# LAN9254_C_P2.net
KiCad netlist of a schematic drawn in Altium Designer
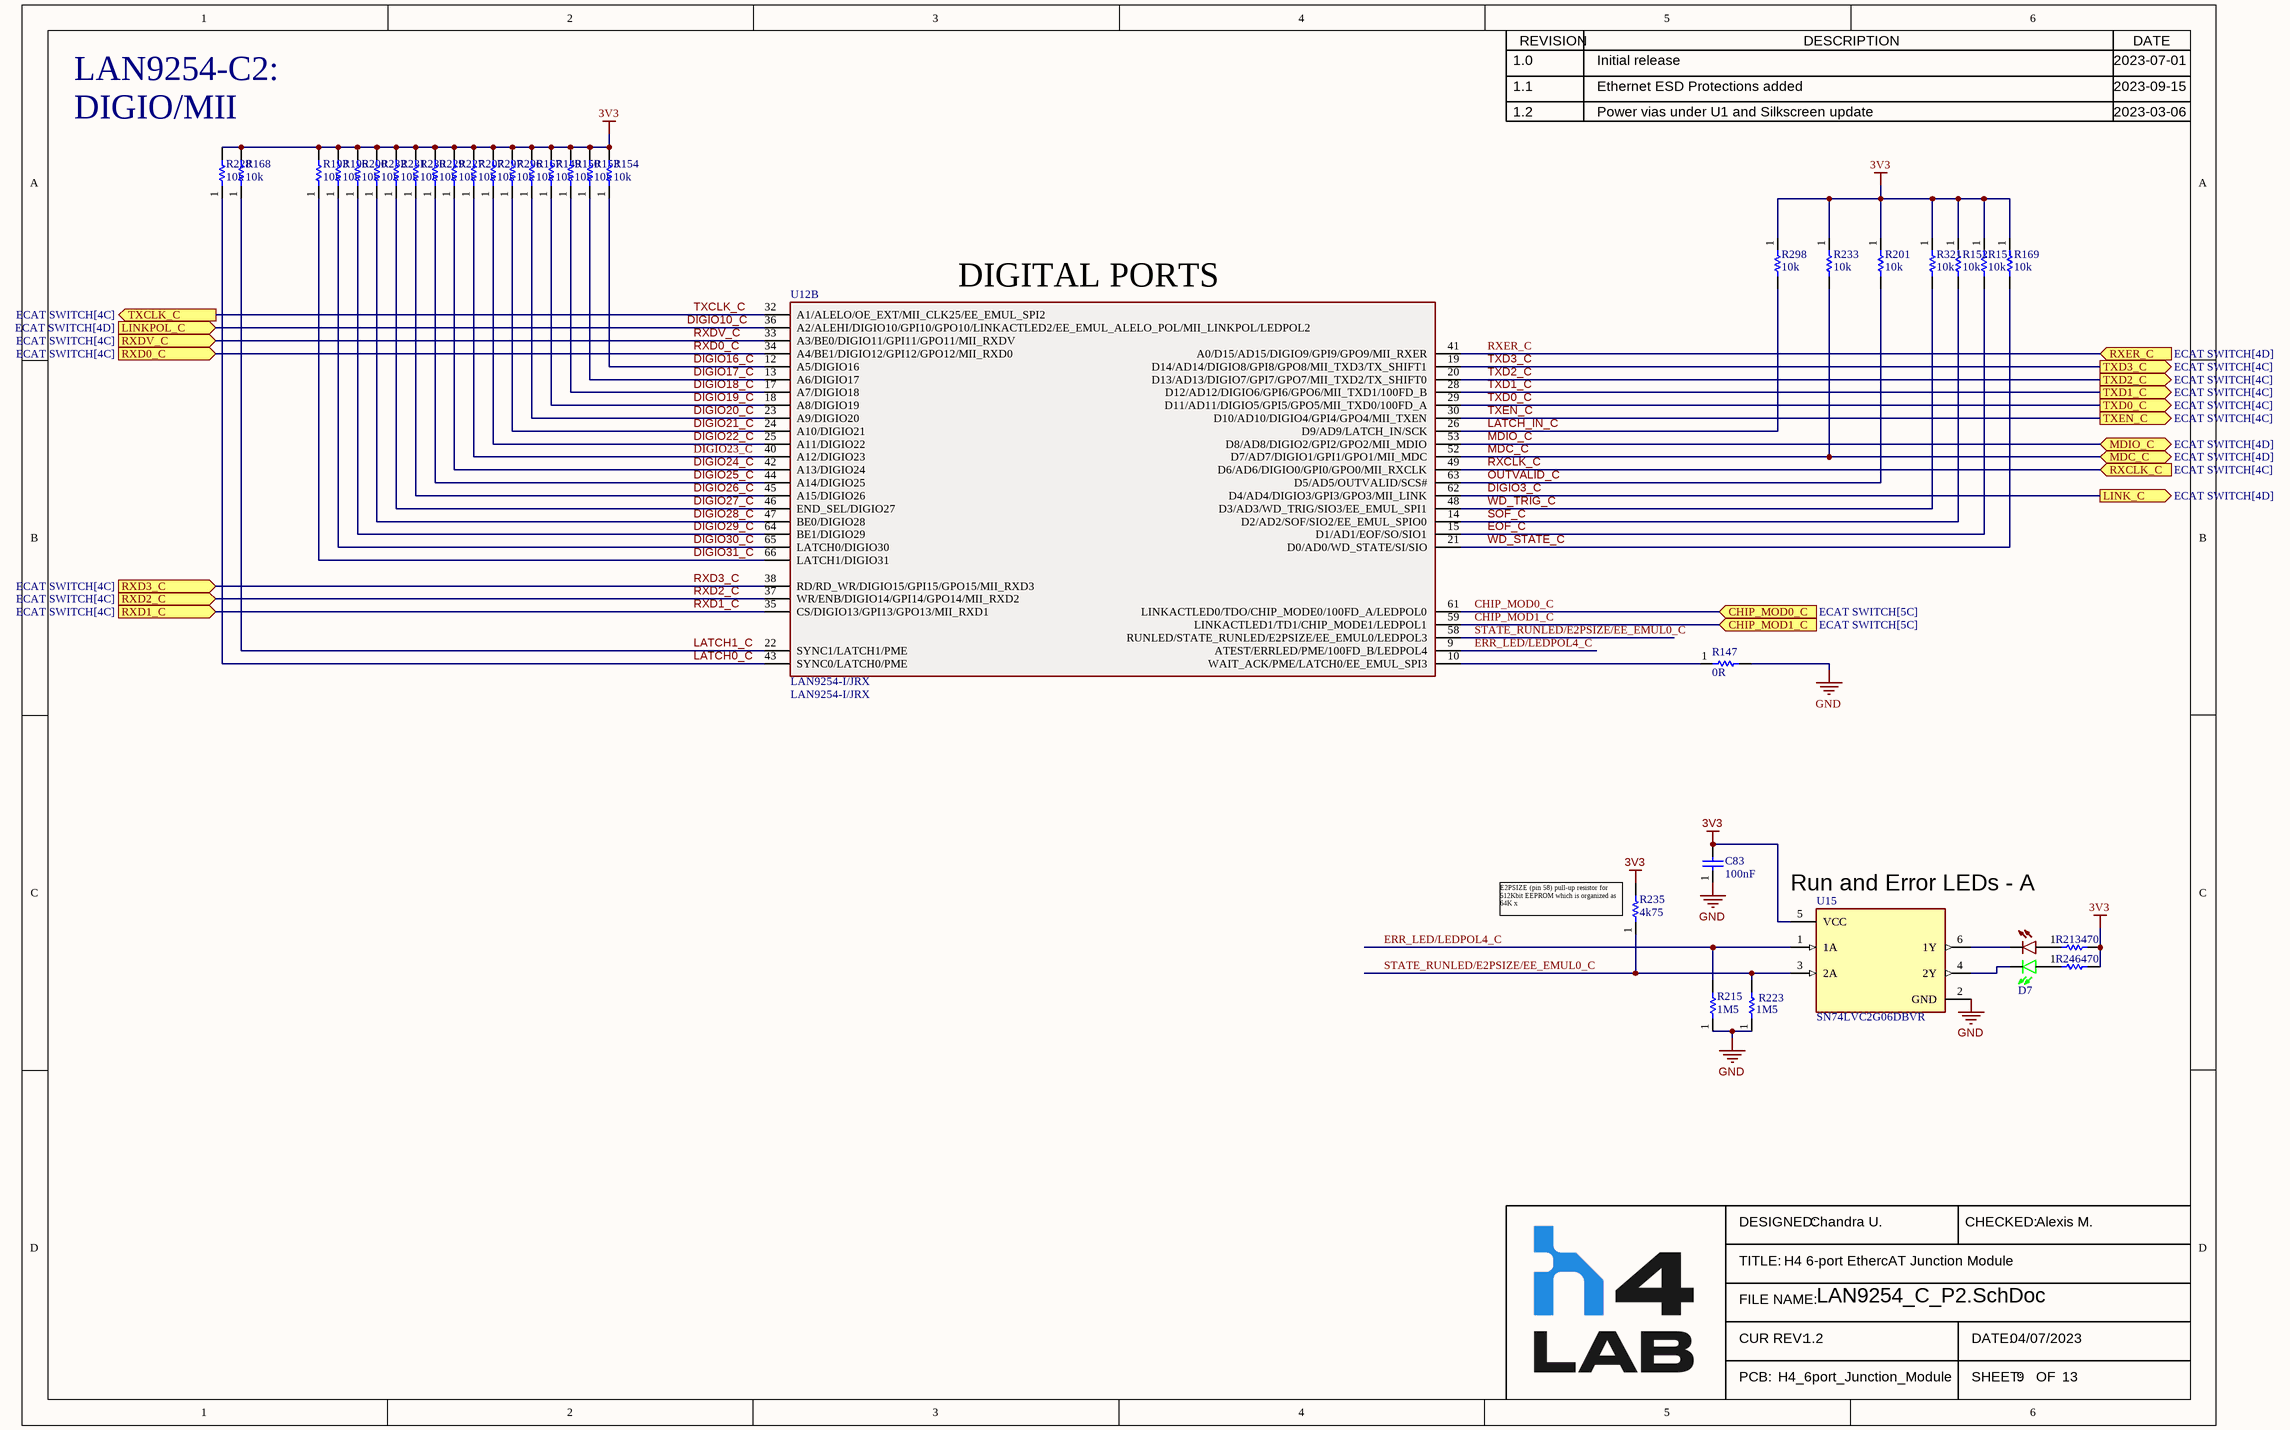
[diagram p0: LAN9254_C_P2.SchDoc]

(export (version "E")
  (design (tool "Eeschema 10.0.6"))
  (components
    (comp (ref "C83")
      (value "100nF")
      (footprint "CAPC1005X03N(0402)")
      (description "CAP CER 0.1UF 16V X7R 0402")
      (fields (field (name "MPN") "GRM155R71C104JA88D") (field (name "TOLERANCE") "5%"))
      (libsource (lib "IHMC_Altium_Lib") (part "100nF_16V_0402_CAP"))
    )
    (comp (ref "D7")
      (value "LTST-C195KGJRKT")
      (footprint "Dual_LED")
      (description "LED GREEN/RED CLEAR CHIP SMD")
      (libsource (lib "IHMC_Altium_Lib") (part "Green/Red_LED"))
    )
    (comp (ref "R147")
      (value "0R")
      (footprint "0402")
      (fields
        (field (name "MANUFACTURER") "Vishay Dale")
        (field (name "MANUFACTURER PART NUMBER") "RCS04020000Z0ED")
      )
      (libsource (lib "IHMC_Altium_Lib") (part "0R_1/5W_0402_RCS04020000Z0ED_RES"))
    )
    (comp (ref "R149")
      (value "10k")
      (footprint "RESC1005X06N(0402)")
      (description "RES SMD 10K OHM 1% 1/16W 0402")
      (fields (field (name "MPN") "RC0402FR-0710KL") (field (name "TOLERANCE") "1%"))
      (libsource (lib "IHMC_Resistors") (part "10k_1/16W_0402_RES"))
    )
    (comp (ref "R150")
      (value "10k")
      (footprint "RESC1005X06N(0402)")
      (description "RES SMD 10K OHM 1% 1/16W 0402")
      (fields (field (name "MPN") "RC0402FR-0710KL") (field (name "TOLERANCE") "1%"))
      (libsource (lib "IHMC_Resistors") (part "10k_1/16W_0402_RES"))
    )
    (comp (ref "R151")
      (value "10k")
      (footprint "RESC1005X06N(0402)")
      (description "RES SMD 10K OHM 1% 1/16W 0402")
      (fields (field (name "MPN") "RC0402FR-0710KL") (field (name "TOLERANCE") "1%"))
      (libsource (lib "IHMC_Resistors") (part "10k_1/16W_0402_RES"))
    )
    (comp (ref "R152")
      (value "10k")
      (footprint "RESC1005X06N(0402)")
      (description "RES SMD 10K OHM 1% 1/16W 0402")
      (fields (field (name "MPN") "RC0402FR-0710KL") (field (name "TOLERANCE") "1%"))
      (libsource (lib "IHMC_Resistors") (part "10k_1/16W_0402_RES"))
    )
    (comp (ref "R153")
      (value "10k")
      (footprint "RESC1005X06N(0402)")
      (description "RES SMD 10K OHM 1% 1/16W 0402")
      (fields (field (name "MPN") "RC0402FR-0710KL") (field (name "TOLERANCE") "1%"))
      (libsource (lib "IHMC_Resistors") (part "10k_1/16W_0402_RES"))
    )
    (comp (ref "R154")
      (value "10k")
      (footprint "RESC1005X06N(0402)")
      (description "RES SMD 10K OHM 1% 1/16W 0402")
      (fields (field (name "MPN") "RC0402FR-0710KL") (field (name "TOLERANCE") "1%"))
      (libsource (lib "IHMC_Resistors") (part "10k_1/16W_0402_RES"))
    )
    (comp (ref "R167")
      (value "10k")
      (footprint "RESC1005X06N(0402)")
      (description "RES SMD 10K OHM 1% 1/16W 0402")
      (fields (field (name "MPN") "RC0402FR-0710KL") (field (name "TOLERANCE") "1%"))
      (libsource (lib "IHMC_Resistors") (part "10k_1/16W_0402_RES"))
    )
    (comp (ref "R168")
      (value "10k")
      (footprint "RESC1005X06N(0402)")
      (description "RES SMD 10K OHM 1% 1/16W 0402")
      (fields (field (name "MPN") "RC0402FR-0710KL") (field (name "TOLERANCE") "1%"))
      (libsource (lib "IHMC_Resistors") (part "10k_1/16W_0402_RES"))
    )
    (comp (ref "R169")
      (value "10k")
      (footprint "RESC1005X06N(0402)")
      (description "RES SMD 10K OHM 1% 1/16W 0402")
      (fields (field (name "MPN") "RC0402FR-0710KL") (field (name "TOLERANCE") "1%"))
      (libsource (lib "IHMC_Resistors") (part "10k_1/16W_0402_RES"))
    )
    (comp (ref "R193")
      (value "10k")
      (footprint "RESC1005X06N(0402)")
      (description "RES SMD 10K OHM 1% 1/16W 0402")
      (fields (field (name "MPN") "RC0402FR-0710KL") (field (name "TOLERANCE") "1%"))
      (libsource (lib "IHMC_Resistors") (part "10k_1/16W_0402_RES"))
    )
    (comp (ref "R196")
      (value "10k")
      (footprint "RESC1005X06N(0402)")
      (description "RES SMD 10K OHM 1% 1/16W 0402")
      (fields (field (name "MPN") "RC0402FR-0710KL") (field (name "TOLERANCE") "1%"))
      (libsource (lib "IHMC_Resistors") (part "10k_1/16W_0402_RES"))
    )
    (comp (ref "R200")
      (value "10k")
      (footprint "RESC1005X06N(0402)")
      (description "RES SMD 10K OHM 1% 1/16W 0402")
      (fields (field (name "MPN") "RC0402FR-0710KL") (field (name "TOLERANCE") "1%"))
      (libsource (lib "IHMC_Resistors") (part "10k_1/16W_0402_RES"))
    )
    (comp (ref "R201")
      (value "10k")
      (footprint "RESC1005X06N(0402)")
      (description "RES SMD 10K OHM 1% 1/16W 0402")
      (fields (field (name "MPN") "RC0402FR-0710KL") (field (name "TOLERANCE") "1%"))
      (libsource (lib "IHMC_Resistors") (part "10k_1/16W_0402_RES"))
    )
    (comp (ref "R207")
      (value "10k")
      (footprint "RESC1005X06N(0402)")
      (description "RES SMD 10K OHM 1% 1/16W 0402")
      (fields (field (name "MPN") "RC0402FR-0710KL") (field (name "TOLERANCE") "1%"))
      (libsource (lib "IHMC_Resistors") (part "10k_1/16W_0402_RES"))
    )
    (comp (ref "R213")
      (value "470")
      (footprint "0402")
      (description "Vishay CRCW Series Thick Film Resistor 0402 Case 470 5% 0.063W 200ppm/K")
      (fields
        (field (name "MANUFACTURER") "Vishay Dale")
        (field (name "MANUFACTURER PART NUMBER") "CRCW0402470RJNED")
      )
      (libsource (lib "IHMC_Altium_Lib") (part "470_1/10W_0402_CRCW0402470RJNED"))
    )
    (comp (ref "R215")
      (value "1M5")
      (footprint "0402")
      (description "RES SMD 1.5M OHM 5% 1/16W 0402")
      (fields
        (field (name "MANUFACTURER") "Vishay Dale")
        (field (name "MANUFACTURER PART NUMBER") "CRCW04021M50JNED")
      )
      (libsource (lib "IHMC_Altium_Lib") (part "1M5_1/16W_0402_CRCW04021M50JNED_RES"))
    )
    (comp (ref "R223")
      (value "1M5")
      (footprint "0402")
      (description "RES SMD 1.5M OHM 5% 1/16W 0402")
      (fields
        (field (name "MANUFACTURER") "Vishay Dale")
        (field (name "MANUFACTURER PART NUMBER") "CRCW04021M50JNED")
      )
      (libsource (lib "IHMC_Altium_Lib") (part "1M5_1/16W_0402_CRCW04021M50JNED_RES"))
    )
    (comp (ref "R227")
      (value "10k")
      (footprint "RESC1005X06N(0402)")
      (description "RES SMD 10K OHM 1% 1/16W 0402")
      (fields (field (name "MPN") "RC0402FR-0710KL") (field (name "TOLERANCE") "1%"))
      (libsource (lib "IHMC_Resistors") (part "10k_1/16W_0402_RES"))
    )
    (comp (ref "R228")
      (value "10k")
      (footprint "RESC1005X06N(0402)")
      (description "RES SMD 10K OHM 1% 1/16W 0402")
      (fields (field (name "MPN") "RC0402FR-0710KL") (field (name "TOLERANCE") "1%"))
      (libsource (lib "IHMC_Resistors") (part "10k_1/16W_0402_RES"))
    )
    (comp (ref "R229")
      (value "10k")
      (footprint "RESC1005X06N(0402)")
      (description "RES SMD 10K OHM 1% 1/16W 0402")
      (fields (field (name "MPN") "RC0402FR-0710KL") (field (name "TOLERANCE") "1%"))
      (libsource (lib "IHMC_Resistors") (part "10k_1/16W_0402_RES"))
    )
    (comp (ref "R230")
      (value "10k")
      (footprint "RESC1005X06N(0402)")
      (description "RES SMD 10K OHM 1% 1/16W 0402")
      (fields (field (name "MPN") "RC0402FR-0710KL") (field (name "TOLERANCE") "1%"))
      (libsource (lib "IHMC_Resistors") (part "10k_1/16W_0402_RES"))
    )
    (comp (ref "R231")
      (value "10k")
      (footprint "RESC1005X06N(0402)")
      (description "RES SMD 10K OHM 1% 1/16W 0402")
      (fields (field (name "MPN") "RC0402FR-0710KL") (field (name "TOLERANCE") "1%"))
      (libsource (lib "IHMC_Resistors") (part "10k_1/16W_0402_RES"))
    )
    (comp (ref "R232")
      (value "10k")
      (footprint "RESC1005X06N(0402)")
      (description "RES SMD 10K OHM 1% 1/16W 0402")
      (fields (field (name "MPN") "RC0402FR-0710KL") (field (name "TOLERANCE") "1%"))
      (libsource (lib "IHMC_Resistors") (part "10k_1/16W_0402_RES"))
    )
    (comp (ref "R233")
      (value "10k")
      (footprint "RESC1005X06N(0402)")
      (description "RES SMD 10K OHM 1% 1/16W 0402")
      (fields (field (name "MPN") "RC0402FR-0710KL") (field (name "TOLERANCE") "1%"))
      (libsource (lib "IHMC_Resistors") (part "10k_1/16W_0402_RES"))
    )
    (comp (ref "R235")
      (value "4k75")
      (footprint "RESC1005X06N(0402)")
      (description "RES SMD 4.75K OHM 1% 1/16W 0402")
      (fields (field (name "MPN") "RC0402FR-074K75L") (field (name "POWER") "1/16"))
      (libsource (lib "IHMC_Altium_Lib") (part "4k75_1/16_0402_RES"))
    )
    (comp (ref "R246")
      (value "470")
      (footprint "0402")
      (description "Vishay CRCW Series Thick Film Resistor 0402 Case 470 5% 0.063W 200ppm/K")
      (fields
        (field (name "MANUFACTURER") "Vishay Dale")
        (field (name "MANUFACTURER PART NUMBER") "CRCW0402470RJNED")
      )
      (libsource (lib "IHMC_Altium_Lib") (part "470_1/10W_0402_CRCW0402470RJNED"))
    )
    (comp (ref "R296")
      (value "10k")
      (footprint "RESC1005X06N(0402)")
      (description "RES SMD 10K OHM 1% 1/16W 0402")
      (fields (field (name "MPN") "RC0402FR-0710KL") (field (name "TOLERANCE") "1%"))
      (libsource (lib "IHMC_Resistors") (part "10k_1/16W_0402_RES"))
    )
    (comp (ref "R297")
      (value "10k")
      (footprint "RESC1005X06N(0402)")
      (description "RES SMD 10K OHM 1% 1/16W 0402")
      (fields (field (name "MPN") "RC0402FR-0710KL") (field (name "TOLERANCE") "1%"))
      (libsource (lib "IHMC_Resistors") (part "10k_1/16W_0402_RES"))
    )
    (comp (ref "R298")
      (value "10k")
      (footprint "RESC1005X06N(0402)")
      (description "RES SMD 10K OHM 1% 1/16W 0402")
      (fields (field (name "MPN") "RC0402FR-0710KL") (field (name "TOLERANCE") "1%"))
      (libsource (lib "IHMC_Resistors") (part "10k_1/16W_0402_RES"))
    )
    (comp (ref "R321")
      (value "10k")
      (footprint "RESC1005X06N(0402)")
      (description "RES SMD 10K OHM 1% 1/16W 0402")
      (fields (field (name "MPN") "RC0402FR-0710KL") (field (name "TOLERANCE") "1%"))
      (libsource (lib "IHMC_Resistors") (part "10k_1/16W_0402_RES"))
    )
    (comp (ref "U12")
      (value "LAN9254-I/JRX")
      (footprint "QFP50P1400X1400X120-81N")
      (description "2/3-PORT Ethercat Slave Controller With 32 Digios With Integrated Ethernet Phys")
      (fields (field (name "MANUFACTURER") "Microchip"))
      (libsource (lib "IHMC_Ethernet") (part "LAN9254-I/JRX"))
    )
    (comp (ref "U15")
      (value "SN74LVC2G06DBVR")
      (footprint "FP-DBV0006A-IPC_C")
      (description "Buffer/Driver 2-CH Inverting Open Drain CMOS 6-Pin SOT-23 T/R")
      (fields (field (name "MANUFACTURER") "Texas Instruments"))
      (libsource (lib "IHMC_Altium_Lib") (part "BUF_dual_SN74LVC2G06DBVR"))
    )
  )
  (nets
    (net (code "1") (name "/CHIP_MOD0_C") (class "Default")
      (node (ref "U12") (pin "61") (pinfunction "LINKACTLED0/TDO/CHIP_MODE0/100FD_A/LEDPOL0_61") (pintype "passive"))
    )
    (net (code "2") (name "/CHIP_MOD1_C") (class "Default")
      (node (ref "U12") (pin "59") (pinfunction "LINKACTLED1/TD1/CHIP_MODE1/LEDPOL1_59") (pintype "passive"))
    )
    (net (code "3") (name "/DIGIO3_C") (class "Default")
      (node (ref "U12") (pin "62") (pinfunction "D4/AD4/DIGIO3/GPI3/GPO3/MII_LINK_62") (pintype "passive"))
    )
    (net (code "4") (name "/DIGIO10_C") (class "Default")
      (node (ref "U12") (pin "36") (pinfunction "A2/ALEHI/DIGIO10/GPI10/GPO10/LINKACTLED2/EE_EMUL_ALELO_POL/MII_LINKPOL/LEDPOL2_36") (pintype "passive"))
    )
    (net (code "5") (name "/DIGIO16_C") (class "Default")
      (node (ref "R154") (pin "1") (pinfunction "1_1") (pintype "passive"))
      (node (ref "U12") (pin "12") (pinfunction "A5/DIGIO16_12") (pintype "passive"))
    )
    (net (code "6") (name "/DIGIO17_C") (class "Default")
      (node (ref "R153") (pin "1") (pinfunction "1_1") (pintype "passive"))
      (node (ref "U12") (pin "13") (pinfunction "A6/DIGIO17_13") (pintype "passive"))
    )
    (net (code "7") (name "/DIGIO18_C") (class "Default")
      (node (ref "R150") (pin "1") (pinfunction "1_1") (pintype "passive"))
      (node (ref "U12") (pin "17") (pinfunction "A7/DIGIO18_17") (pintype "passive"))
    )
    (net (code "8") (name "/DIGIO19_C") (class "Default")
      (node (ref "R149") (pin "1") (pinfunction "1_1") (pintype "passive"))
      (node (ref "U12") (pin "18") (pinfunction "A8/DIGIO19_18") (pintype "passive"))
    )
    (net (code "9") (name "/DIGIO20_C") (class "Default")
      (node (ref "R167") (pin "1") (pinfunction "1_1") (pintype "passive"))
      (node (ref "U12") (pin "23") (pinfunction "A9/DIGIO20_23") (pintype "passive"))
    )
    (net (code "10") (name "/DIGIO21_C") (class "Default")
      (node (ref "R296") (pin "1") (pinfunction "1_1") (pintype "passive"))
      (node (ref "U12") (pin "24") (pinfunction "A10/DIGIO21_24") (pintype "passive"))
    )
    (net (code "11") (name "/DIGIO22_C") (class "Default")
      (node (ref "R297") (pin "1") (pinfunction "1_1") (pintype "passive"))
      (node (ref "U12") (pin "25") (pinfunction "A11/DIGIO22_25") (pintype "passive"))
    )
    (net (code "12") (name "/DIGIO23_C") (class "Default")
      (node (ref "R207") (pin "1") (pinfunction "1_1") (pintype "passive"))
      (node (ref "U12") (pin "40") (pinfunction "A12/DIGIO23_40") (pintype "passive"))
    )
    (net (code "13") (name "/DIGIO24_C") (class "Default")
      (node (ref "R227") (pin "1") (pinfunction "1_1") (pintype "passive"))
      (node (ref "U12") (pin "42") (pinfunction "A13/DIGIO24_42") (pintype "passive"))
    )
    (net (code "14") (name "/DIGIO25_C") (class "Default")
      (node (ref "R229") (pin "1") (pinfunction "1_1") (pintype "passive"))
      (node (ref "U12") (pin "44") (pinfunction "A14/DIGIO25_44") (pintype "passive"))
    )
    (net (code "15") (name "/DIGIO26_C") (class "Default")
      (node (ref "R230") (pin "1") (pinfunction "1_1") (pintype "passive"))
      (node (ref "U12") (pin "45") (pinfunction "A15/DIGIO26_45") (pintype "passive"))
    )
    (net (code "16") (name "/DIGIO27_C") (class "Default")
      (node (ref "R231") (pin "1") (pinfunction "1_1") (pintype "passive"))
      (node (ref "U12") (pin "46") (pinfunction "END_SEL/DIGIO27_46") (pintype "passive"))
    )
    (net (code "17") (name "/DIGIO28_C") (class "Default")
      (node (ref "R232") (pin "1") (pinfunction "1_1") (pintype "passive"))
      (node (ref "U12") (pin "47") (pinfunction "BE0/DIGIO28_47") (pintype "passive"))
    )
    (net (code "18") (name "/DIGIO29_C") (class "Default")
      (node (ref "R200") (pin "1") (pinfunction "1_1") (pintype "passive"))
      (node (ref "U12") (pin "64") (pinfunction "BE1/DIGIO29_64") (pintype "passive"))
    )
    (net (code "19") (name "/DIGIO30_C") (class "Default")
      (node (ref "R196") (pin "1") (pinfunction "1_1") (pintype "passive"))
      (node (ref "U12") (pin "65") (pinfunction "LATCH0/DIGIO30_65") (pintype "passive"))
    )
    (net (code "20") (name "/DIGIO31_C") (class "Default")
      (node (ref "R193") (pin "1") (pinfunction "1_1") (pintype "passive"))
      (node (ref "U12") (pin "66") (pinfunction "LATCH1/DIGIO31_66") (pintype "passive"))
    )
    (net (code "21") (name "/EOF_C") (class "Default")
      (node (ref "R151") (pin "2") (pinfunction "2_2") (pintype "passive"))
      (node (ref "U12") (pin "15") (pinfunction "D1/AD1/EOF/SO/SIO1_15") (pintype "passive"))
    )
    (net (code "22") (name "/ERR_LED{slash}LEDPOL4_C") (class "Default")
      (node (ref "R215") (pin "2") (pinfunction "2_2") (pintype "passive"))
      (node (ref "U12") (pin "9") (pinfunction "ATEST/ERRLED/PME/100FD_B/LEDPOL4_9") (pintype "passive"))
      (node (ref "U15") (pin "1") (pinfunction "1A_1") (pintype "input"))
    )
    (net (code "23") (name "/LATCH0_C") (class "Default")
      (node (ref "R228") (pin "1") (pinfunction "1_1") (pintype "passive"))
      (node (ref "U12") (pin "43") (pinfunction "SYNC0/LATCH0/PME_43") (pintype "passive"))
    )
    (net (code "24") (name "/LATCH1_C") (class "Default")
      (node (ref "R168") (pin "1") (pinfunction "1_1") (pintype "passive"))
      (node (ref "U12") (pin "22") (pinfunction "SYNC1/LATCH1/PME_22") (pintype "passive"))
    )
    (net (code "25") (name "/LATCH_IN_C") (class "Default")
      (node (ref "R298") (pin "2") (pinfunction "2_2") (pintype "passive"))
      (node (ref "U12") (pin "26") (pinfunction "D9/AD9/LATCH_IN/SCK_26") (pintype "passive"))
    )
    (net (code "26") (name "/MDC_C") (class "Default")
      (node (ref "R233") (pin "2") (pinfunction "2_2") (pintype "passive"))
      (node (ref "U12") (pin "52") (pinfunction "D7/AD7/DIGIO1/GPI1/GPO1/MII_MDC_52") (pintype "passive"))
    )
    (net (code "27") (name "/MDIO_C") (class "Default")
      (node (ref "U12") (pin "53") (pinfunction "D8/AD8/DIGIO2/GPI2/GPO2/MII_MDIO_53") (pintype "passive"))
    )
    (net (code "28") (name "/OUTVALID_C") (class "Default")
      (node (ref "R201") (pin "2") (pinfunction "2_2") (pintype "passive"))
      (node (ref "U12") (pin "63") (pinfunction "D5/AD5/OUTVALID/SCS#_63") (pintype "passive"))
    )
    (net (code "29") (name "/RXCLK_C") (class "Default")
      (node (ref "U12") (pin "49") (pinfunction "D6/AD6/DIGIO0/GPI0/GPO0/MII_RXCLK_49") (pintype "passive"))
    )
    (net (code "30") (name "/RXD0_C") (class "Default")
      (node (ref "U12") (pin "34") (pinfunction "A4/BE1/DIGIO12/GPI12/GPO12/MII_RXD0_34") (pintype "passive"))
    )
    (net (code "31") (name "/RXD1_C") (class "Default")
      (node (ref "U12") (pin "35") (pinfunction "CS/DIGIO13/GPI13/GPO13/MII_RXD1_35") (pintype "passive"))
    )
    (net (code "32") (name "/RXD2_C") (class "Default")
      (node (ref "U12") (pin "37") (pinfunction "WR/ENB/DIGIO14/GPI14/GPO14/MII_RXD2_37") (pintype "passive"))
    )
    (net (code "33") (name "/RXD3_C") (class "Default")
      (node (ref "U12") (pin "38") (pinfunction "RD/RD_WR/DIGIO15/GPI15/GPO15/MII_RXD3_38") (pintype "passive"))
    )
    (net (code "34") (name "/RXDV_C") (class "Default")
      (node (ref "U12") (pin "33") (pinfunction "A3/BE0/DIGIO11/GPI11/GPO11/MII_RXDV_33") (pintype "passive"))
    )
    (net (code "35") (name "/RXER_C") (class "Default")
      (node (ref "U12") (pin "41") (pinfunction "A0/D15/AD15/DIGIO9/GPI9/GPO9/MII_RXER_41") (pintype "passive"))
    )
    (net (code "36") (name "/SOF_C") (class "Default")
      (node (ref "R152") (pin "2") (pinfunction "2_2") (pintype "passive"))
      (node (ref "U12") (pin "14") (pinfunction "D2/AD2/SOF/SIO2/EE_EMUL_SPIO0_14") (pintype "passive"))
    )
    (net (code "37") (name "/STATE_RUNLED{slash}E2PSIZE{slash}EE_EMUL0_C") (class "Default")
      (node (ref "R223") (pin "2") (pinfunction "2_2") (pintype "passive"))
      (node (ref "R235") (pin "1") (pinfunction "1_1") (pintype "passive"))
      (node (ref "U12") (pin "58") (pinfunction "RUNLED/STATE_RUNLED/E2PSIZE/EE_EMUL0/LEDPOL3_58") (pintype "passive"))
      (node (ref "U15") (pin "3") (pinfunction "2A_3") (pintype "input"))
    )
    (net (code "38") (name "/TXCLK_C") (class "Default")
      (node (ref "U12") (pin "32") (pinfunction "A1/ALELO/OE_EXT/MII_CLK25/EE_EMUL_SPI2_32") (pintype "passive"))
    )
    (net (code "39") (name "/TXD0_C") (class "Default")
      (node (ref "U12") (pin "29") (pinfunction "D11/AD11/DIGIO5/GPI5/GPO5/MII_TXD0/100FD_A_29") (pintype "passive"))
    )
    (net (code "40") (name "/TXD1_C") (class "Default")
      (node (ref "U12") (pin "28") (pinfunction "D12/AD12/DIGIO6/GPI6/GPO6/MII_TXD1/100FD_B_28") (pintype "passive"))
    )
    (net (code "41") (name "/TXD2_C") (class "Default")
      (node (ref "U12") (pin "20") (pinfunction "D13/AD13/DIGIO7/GPI7/GPO7/MII_TXD2/TX_SHIFT0_20") (pintype "passive"))
    )
    (net (code "42") (name "/TXD3_C") (class "Default")
      (node (ref "U12") (pin "19") (pinfunction "D14/AD14/DIGIO8/GPI8/GPO8/MII_TXD3/TX_SHIFT1_19") (pintype "passive"))
    )
    (net (code "43") (name "/TXEN_C") (class "Default")
      (node (ref "U12") (pin "30") (pinfunction "D10/AD10/DIGIO4/GPI4/GPO4/MII_TXEN_30") (pintype "passive"))
    )
    (net (code "44") (name "/WD_STATE_C") (class "Default")
      (node (ref "R169") (pin "2") (pinfunction "2_2") (pintype "passive"))
      (node (ref "U12") (pin "21") (pinfunction "D0/AD0/WD_STATE/SI/SIO_21") (pintype "passive"))
    )
    (net (code "45") (name "/WD_TRIG_C") (class "Default")
      (node (ref "R321") (pin "2") (pinfunction "2_2") (pintype "passive"))
      (node (ref "U12") (pin "48") (pinfunction "D3/AD3/WD_TRIG/SIO3/EE_EMUL_SPI1_48") (pintype "passive"))
    )
    (net (code "46") (name "3V3") (class "Default")
      (node (ref "C83") (pin "2") (pinfunction "2_2") (pintype "passive"))
      (node (ref "R149") (pin "2") (pinfunction "2_2") (pintype "passive"))
      (node (ref "R150") (pin "2") (pinfunction "2_2") (pintype "passive"))
      (node (ref "R151") (pin "1") (pinfunction "1_1") (pintype "passive"))
      (node (ref "R152") (pin "1") (pinfunction "1_1") (pintype "passive"))
      (node (ref "R153") (pin "2") (pinfunction "2_2") (pintype "passive"))
      (node (ref "R154") (pin "2") (pinfunction "2_2") (pintype "passive"))
      (node (ref "R167") (pin "2") (pinfunction "2_2") (pintype "passive"))
      (node (ref "R168") (pin "2") (pinfunction "2_2") (pintype "passive"))
      (node (ref "R169") (pin "1") (pinfunction "1_1") (pintype "passive"))
      (node (ref "R193") (pin "2") (pinfunction "2_2") (pintype "passive"))
      (node (ref "R196") (pin "2") (pinfunction "2_2") (pintype "passive"))
      (node (ref "R200") (pin "2") (pinfunction "2_2") (pintype "passive"))
      (node (ref "R201") (pin "1") (pinfunction "1_1") (pintype "passive"))
      (node (ref "R207") (pin "2") (pinfunction "2_2") (pintype "passive"))
      (node (ref "R213") (pin "2") (pinfunction "2_2") (pintype "passive"))
      (node (ref "R227") (pin "2") (pinfunction "2_2") (pintype "passive"))
      (node (ref "R228") (pin "2") (pinfunction "2_2") (pintype "passive"))
      (node (ref "R229") (pin "2") (pinfunction "2_2") (pintype "passive"))
      (node (ref "R230") (pin "2") (pinfunction "2_2") (pintype "passive"))
      (node (ref "R231") (pin "2") (pinfunction "2_2") (pintype "passive"))
      (node (ref "R232") (pin "2") (pinfunction "2_2") (pintype "passive"))
      (node (ref "R233") (pin "1") (pinfunction "1_1") (pintype "passive"))
      (node (ref "R235") (pin "2") (pinfunction "2_2") (pintype "passive"))
      (node (ref "R246") (pin "2") (pinfunction "2_2") (pintype "passive"))
      (node (ref "R296") (pin "2") (pinfunction "2_2") (pintype "passive"))
      (node (ref "R297") (pin "2") (pinfunction "2_2") (pintype "passive"))
      (node (ref "R298") (pin "1") (pinfunction "1_1") (pintype "passive"))
      (node (ref "R321") (pin "1") (pinfunction "1_1") (pintype "passive"))
      (node (ref "U15") (pin "5") (pinfunction "VCC_5") (pintype "power_in"))
    )
    (net (code "47") (name "GND") (class "Default")
      (node (ref "C83") (pin "1") (pinfunction "1_1") (pintype "passive"))
      (node (ref "R147") (pin "2") (pinfunction "2_2") (pintype "passive"))
      (node (ref "R215") (pin "1") (pinfunction "1_1") (pintype "passive"))
      (node (ref "R223") (pin "1") (pinfunction "1_1") (pintype "passive"))
      (node (ref "U15") (pin "2") (pinfunction "GND_2") (pintype "power_in"))
    )
    (net (code "48") (name "Net-(D7-Pad1)") (class "Default")
      (node (ref "D7") (pin "1") (pinfunction "1_1") (pintype "passive"))
      (node (ref "R246") (pin "1") (pinfunction "1_1") (pintype "passive"))
    )
    (net (code "49") (name "Net-(D7-Pad2)") (class "Default")
      (node (ref "D7") (pin "2") (pinfunction "2_2") (pintype "passive"))
      (node (ref "R213") (pin "1") (pinfunction "1_1") (pintype "passive"))
    )
    (net (code "50") (name "Net-(U12B-WAIT_ACK{slash}PME{slash}LATCH0{slash}EE_EMUL_SPI3)") (class "Default")
      (node (ref "R147") (pin "1") (pinfunction "1_1") (pintype "passive"))
      (node (ref "U12") (pin "10") (pinfunction "WAIT_ACK/PME/LATCH0/EE_EMUL_SPI3_10") (pintype "passive"))
    )
    (net (code "51") (name "Net-(U15-1Y)") (class "Default")
      (node (ref "D7") (pin "4") (pinfunction "4_4") (pintype "passive"))
      (node (ref "U15") (pin "6") (pinfunction "1Y_6") (pintype "output"))
    )
    (net (code "52") (name "Net-(U15-2Y)") (class "Default")
      (node (ref "D7") (pin "3") (pinfunction "3_3") (pintype "passive"))
      (node (ref "U15") (pin "4") (pinfunction "2Y_4") (pintype "output"))
    )
  )
)
